# 03__EFR32_Signal_Assignments.net
KiCad netlist of a schematic drawn in Altium Designer
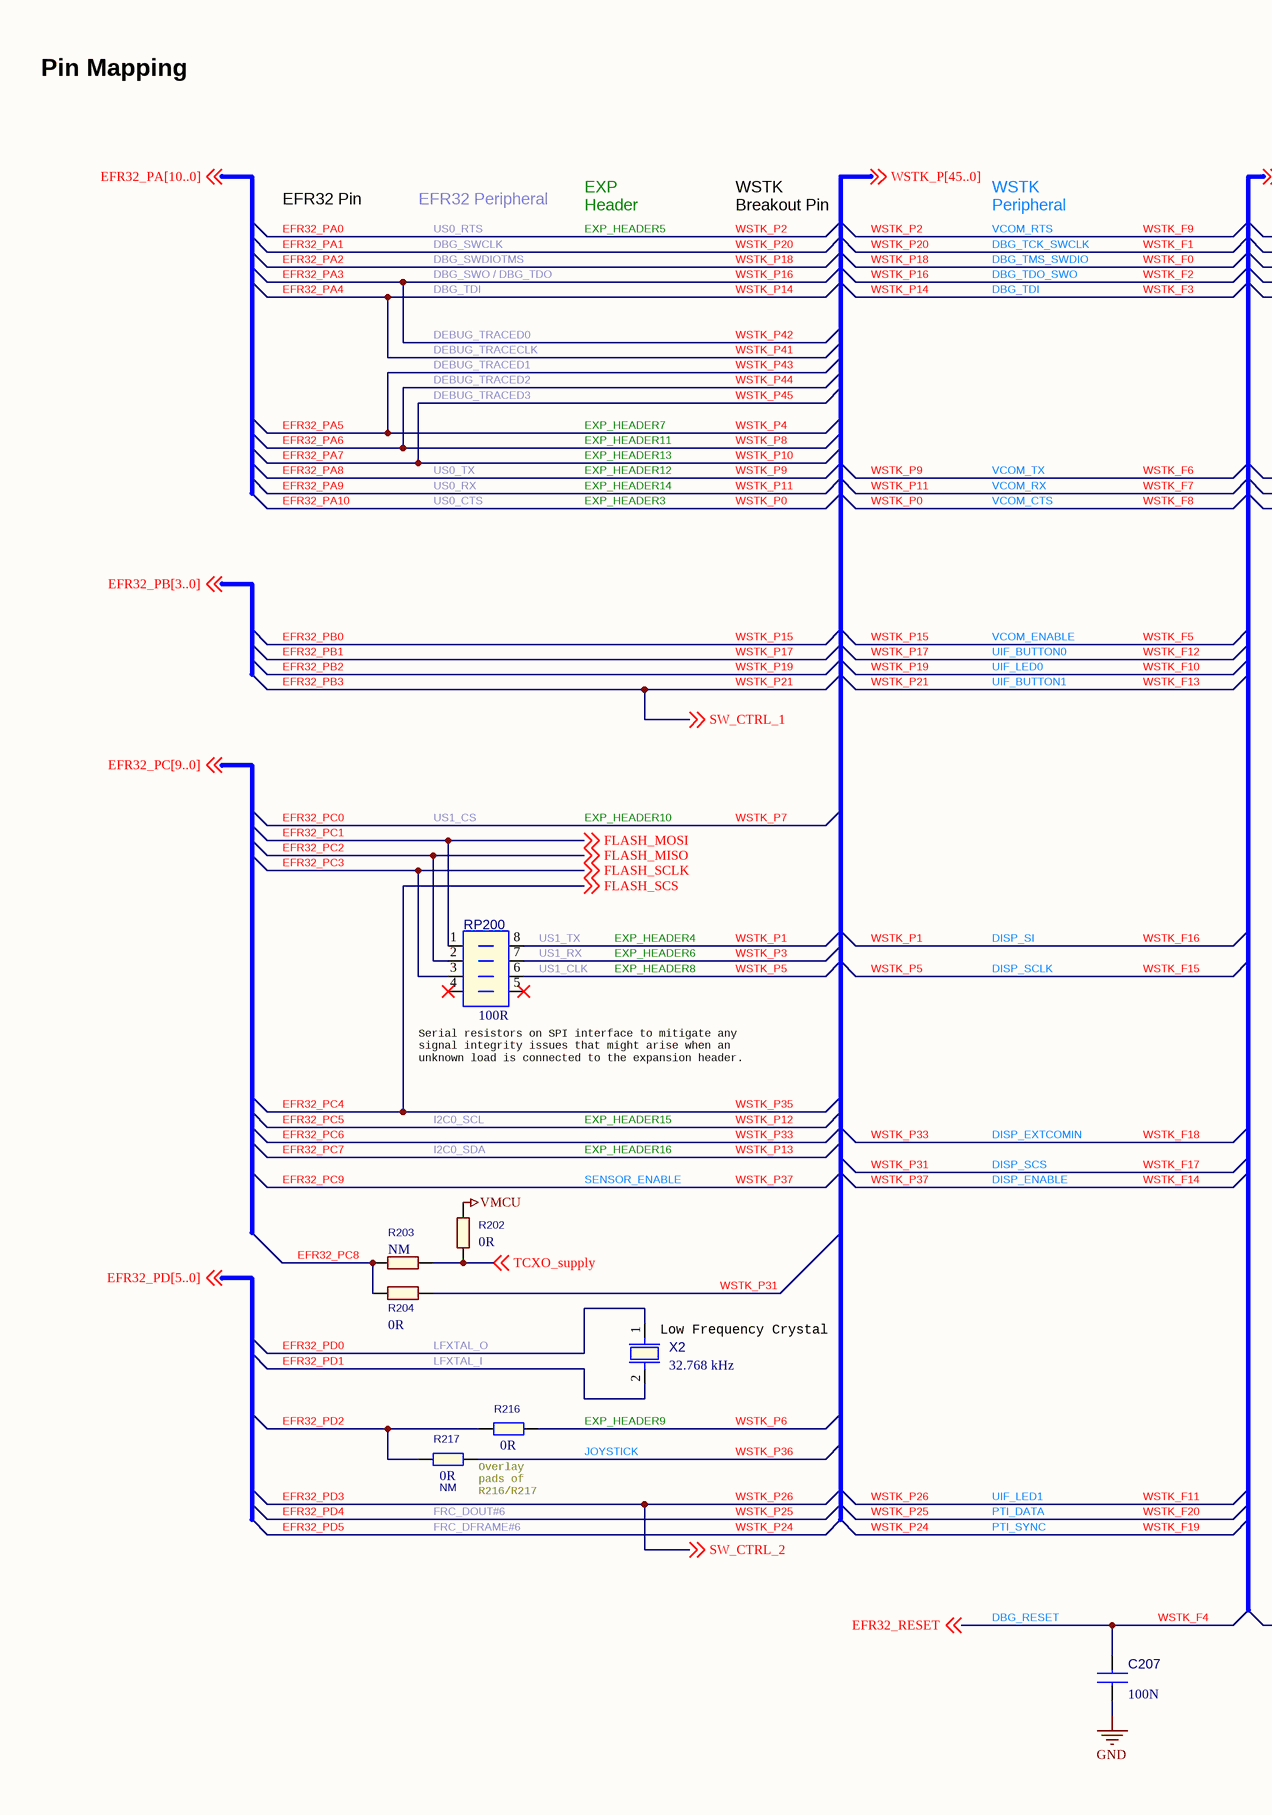
[diagram p0: 03_ EFR32 Signal Assignments.SchDoc, left]
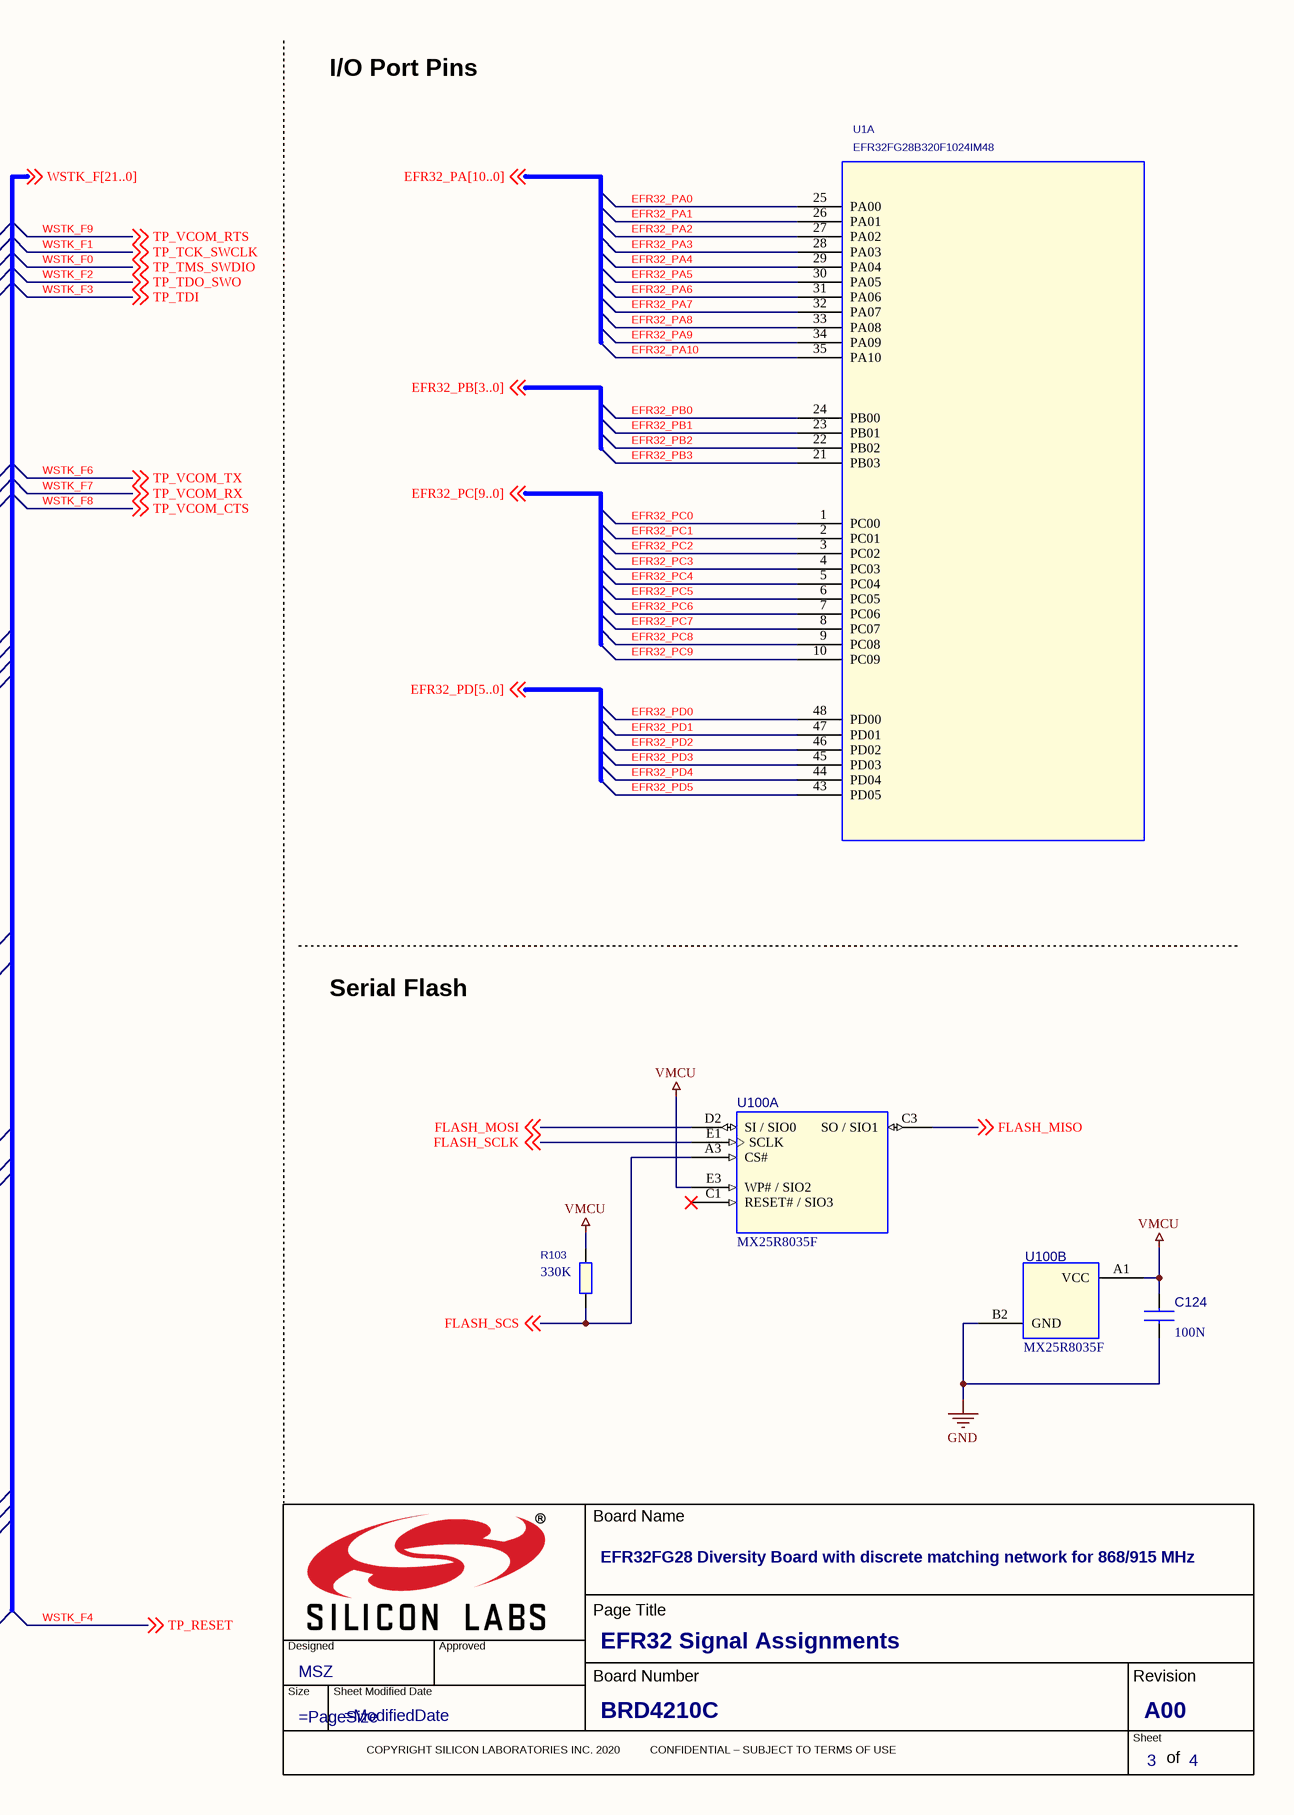
[diagram p1: 03_ EFR32 Signal Assignments.SchDoc, right]

(export (version "E")
  (design (tool "Eeschema 10.0.6"))
  (components
    (comp (ref "C124")
      (value "100N")
      (footprint "C0201_L")
      (fields (field (name "TOLERANCE") "20%"))
      (libsource (lib "*") (part "C0201"))
    )
    (comp (ref "C207")
      (value "100N")
      (footprint "C0201_L")
      (fields (field (name "TOLERANCE") "20%"))
      (libsource (lib "*") (part "C0201"))
    )
    (comp (ref "R103") (value "330K") (footprint "R0201_L") (libsource (lib "*") (part "R0201")))
    (comp (ref "R202") (value "0R") (footprint "R0201_L") (libsource (lib "") (part "R0201_1")))
    (comp (ref "R203") (value "NM") (footprint "R0201_L") (libsource (lib "BRD4210A_Library") (part "R0201")))
    (comp (ref "R204") (value "0R") (footprint "R0201_L") (libsource (lib "BRD4210A_Library") (part "R0201")))
    (comp (ref "R216") (value "0R") (footprint "R0402_L") (libsource (lib "*") (part "R0402")))
    (comp (ref "R217")
      (value "0R")
      (footprint "R0402_L")
      (fields (field (name "NOT MOUNTED") "NM"))
      (libsource (lib "*") (part "R0402"))
    )
    (comp (ref "RP200")
      (value "100R")
      (footprint "RES_MNR04-8")
      (fields (field (name "MFG") "ROHM"))
      (libsource (lib "*") (part "MNR04M0APJ101"))
    )
    (comp (ref "U1")
      (value "EFR32FG28B320F1024IM48")
      (footprint "QFN48_M040_6.0X6.0_EP_SL")
      (fields (field (name "MFG") "Silicon Labs"))
      (libsource (lib "*") (part "EFR32xG23_QFN48"))
    )
    (comp (ref "U100")
      (value "MX25R8035F")
      (footprint "BGA8_M040_1.24x1.75_WLCSP")
      (fields (field (name "MFG") "Macronix"))
      (libsource (lib "*") (part "MX25R8035"))
    )
    (comp (ref "X2")
      (value "32.768 kHz")
      (footprint "X_MCS_CM8V-T1A")
      (fields (field (name "MFG") "Micro Crystal AG"))
      (libsource (lib "*") (part "CM8V-T1A"))
    )
  )
  (nets
    (net (code "3") (name "EFR32_PC8") (class "Default")
      (node (ref "R203") (pin "2") (pinfunction "2_2") (pintype "passive"))
      (node (ref "R204") (pin "2") (pinfunction "2_2") (pintype "passive"))
      (node (ref "U1") (pin "9") (pinfunction "PC08_9") (pintype "passive"))
    )
    (net (code "5") (name "EFR32_PD0") (class "Default")
      (node (ref "U1") (pin "48") (pinfunction "PD00_48") (pintype "passive"))
      (node (ref "X2") (pin "1") (pinfunction "1_1") (pintype "passive"))
    )
    (net (code "6") (name "EFR32_PD1") (class "Default")
      (node (ref "U1") (pin "47") (pinfunction "PD01_47") (pintype "passive"))
      (node (ref "X2") (pin "2") (pinfunction "2_2") (pintype "passive"))
    )
    (net (code "7") (name "EFR32_PD2") (class "Default")
      (node (ref "R216") (pin "1") (pinfunction "1_1") (pintype "passive"))
      (node (ref "R217") (pin "1") (pinfunction "1_1") (pintype "passive"))
      (node (ref "U1") (pin "46") (pinfunction "PD02_46") (pintype "passive"))
    )
    (net (code "9") (name "EFR32_RESET") (class "Default")
      (node (ref "C207") (pin "1") (pinfunction "1_1") (pintype "passive"))
    )
    (net (code "10") (name "FLASH_MISO") (class "Default")
      (node (ref "RP200") (pin "2") (pinfunction "R12_2") (pintype "passive"))
      (node (ref "U1") (pin "3") (pinfunction "PC02_3") (pintype "passive"))
      (node (ref "U100") (pin "C3") (pinfunction "SO_/_SIO1_C3") (pintype "bidirectional"))
    )
    (net (code "11") (name "FLASH_MOSI") (class "Default")
      (node (ref "RP200") (pin "1") (pinfunction "R11_1") (pintype "passive"))
      (node (ref "U1") (pin "2") (pinfunction "PC01_2") (pintype "passive"))
      (node (ref "U100") (pin "D2") (pinfunction "SI_/_SIO0_D2") (pintype "bidirectional"))
    )
    (net (code "12") (name "FLASH_SCLK") (class "Default")
      (node (ref "RP200") (pin "3") (pinfunction "R13_3") (pintype "passive"))
      (node (ref "U1") (pin "4") (pinfunction "PC03_4") (pintype "passive"))
      (node (ref "U100") (pin "E1") (pinfunction "SCLK_E1") (pintype "input"))
    )
    (net (code "13") (name "FLASH_SCS") (class "Default")
      (node (ref "R103") (pin "1") (pinfunction "1_1") (pintype "passive"))
      (node (ref "U1") (pin "5") (pinfunction "PC04_5") (pintype "passive"))
      (node (ref "U100") (pin "A3") (pinfunction "CS#_A3") (pintype "input"))
    )
    (net (code "14") (name "GND") (class "Default")
      (node (ref "C124") (pin "2") (pinfunction "2_2") (pintype "passive"))
      (node (ref "C207") (pin "2") (pinfunction "2_2") (pintype "passive"))
      (node (ref "U100") (pin "B2") (pinfunction "GND_B2") (pintype "power_in"))
    )
    (net (code "15") (name "SW_CTRL_1") (class "Default")
      (node (ref "U1") (pin "21") (pinfunction "PB03_21") (pintype "passive"))
    )
    (net (code "16") (name "SW_CTRL_2") (class "Default")
      (node (ref "U1") (pin "45") (pinfunction "PD03_45") (pintype "passive"))
    )
    (net (code "17") (name "TCXO_supply") (class "Default")
      (node (ref "R202") (pin "1") (pinfunction "1_1") (pintype "passive"))
      (node (ref "R203") (pin "1") (pinfunction "1_1") (pintype "passive"))
    )
    (net (code "18") (name "TP_TCK_SWCLK") (class "Default")
      (node (ref "U1") (pin "26") (pinfunction "PA01_26") (pintype "passive"))
    )
    (net (code "19") (name "TP_TDI") (class "Default")
      (node (ref "U1") (pin "29") (pinfunction "PA04_29") (pintype "passive"))
    )
    (net (code "20") (name "TP_TDO_SWO") (class "Default")
      (node (ref "U1") (pin "28") (pinfunction "PA03_28") (pintype "passive"))
    )
    (net (code "21") (name "TP_TMS_SWDIO") (class "Default")
      (node (ref "U1") (pin "27") (pinfunction "PA02_27") (pintype "passive"))
    )
    (net (code "22") (name "TP_VCOM_CTS") (class "Default")
      (node (ref "U1") (pin "35") (pinfunction "PA10_35") (pintype "passive"))
    )
    (net (code "23") (name "TP_VCOM_RTS") (class "Default")
      (node (ref "U1") (pin "25") (pinfunction "PA00_25") (pintype "passive"))
    )
    (net (code "24") (name "TP_VCOM_RX") (class "Default")
      (node (ref "U1") (pin "34") (pinfunction "PA09_34") (pintype "passive"))
    )
    (net (code "25") (name "TP_VCOM_TX") (class "Default")
      (node (ref "U1") (pin "33") (pinfunction "PA08_33") (pintype "passive"))
    )
    (net (code "26") (name "VMCU") (class "Default")
      (node (ref "C124") (pin "1") (pinfunction "1_1") (pintype "passive"))
      (node (ref "R103") (pin "2") (pinfunction "2_2") (pintype "passive"))
      (node (ref "R202") (pin "2") (pinfunction "2_2") (pintype "passive"))
      (node (ref "U100") (pin "A1") (pinfunction "VCC_A1") (pintype "power_in"))
      (node (ref "U100") (pin "E3") (pinfunction "WP#_/_SIO2_E3") (pintype "input"))
    )
    (net (code "27") (name "WSTK_F5") (class "Default")
      (node (ref "U1") (pin "24") (pinfunction "PB00_24") (pintype "passive"))
    )
    (net (code "28") (name "WSTK_F10") (class "Default")
      (node (ref "U1") (pin "22") (pinfunction "PB02_22") (pintype "passive"))
    )
    (net (code "29") (name "WSTK_F12") (class "Default")
      (node (ref "U1") (pin "23") (pinfunction "PB01_23") (pintype "passive"))
    )
    (net (code "30") (name "WSTK_F14") (class "Default")
      (node (ref "U1") (pin "10") (pinfunction "PC09_10") (pintype "passive"))
    )
    (net (code "31") (name "WSTK_F15") (class "Default")
      (node (ref "RP200") (pin "6") (pinfunction "R16_6") (pintype "passive"))
    )
    (net (code "32") (name "WSTK_F16") (class "Default")
      (node (ref "RP200") (pin "8") (pinfunction "R18_8") (pintype "passive"))
    )
    (net (code "33") (name "WSTK_F17") (class "Default")
      (node (ref "R204") (pin "1") (pinfunction "1_1") (pintype "passive"))
    )
    (net (code "34") (name "WSTK_F18") (class "Default")
      (node (ref "U1") (pin "7") (pinfunction "PC06_7") (pintype "passive"))
    )
    (net (code "35") (name "WSTK_F19") (class "Default")
      (node (ref "U1") (pin "43") (pinfunction "PD05_43") (pintype "passive"))
    )
    (net (code "36") (name "WSTK_F20") (class "Default")
      (node (ref "U1") (pin "44") (pinfunction "PD04_44") (pintype "passive"))
    )
    (net (code "38") (name "WSTK_P3") (class "Default")
      (node (ref "RP200") (pin "7") (pinfunction "R17_7") (pintype "passive"))
    )
    (net (code "39") (name "WSTK_P6") (class "Default")
      (node (ref "R216") (pin "2") (pinfunction "2_2") (pintype "passive"))
    )
    (net (code "40") (name "WSTK_P7") (class "Default")
      (node (ref "U1") (pin "1") (pinfunction "PC00_1") (pintype "passive"))
    )
    (net (code "41") (name "WSTK_P8") (class "Default")
      (node (ref "U1") (pin "31") (pinfunction "PA06_31") (pintype "passive"))
    )
    (net (code "42") (name "WSTK_P12") (class "Default")
      (node (ref "U1") (pin "6") (pinfunction "PC05_6") (pintype "passive"))
    )
    (net (code "43") (name "WSTK_P13") (class "Default")
      (node (ref "U1") (pin "8") (pinfunction "PC07_8") (pintype "passive"))
    )
    (net (code "44") (name "WSTK_P36") (class "Default")
      (node (ref "R217") (pin "2") (pinfunction "2_2") (pintype "passive"))
    )
    (net (code "45") (name "WSTK_P43") (class "Default")
      (node (ref "U1") (pin "30") (pinfunction "PA05_30") (pintype "passive"))
    )
    (net (code "46") (name "WSTK_P45") (class "Default")
      (node (ref "U1") (pin "32") (pinfunction "PA07_32") (pintype "passive"))
    )
    (net (code "48") (name "unconnected-(RP200-R14-Pad4)") (class "Default")
      (node (ref "RP200") (pin "4") (pinfunction "R14_4") (pintype "passive+no_connect"))
    )
    (net (code "49") (name "unconnected-(RP200-R15-Pad5)") (class "Default")
      (node (ref "RP200") (pin "5") (pinfunction "R15_5") (pintype "passive+no_connect"))
    )
    (net (code "50") (name "unconnected-(U100A-RESET#_{slash}_SIO3-PadC1)") (class "Default")
      (node (ref "U100") (pin "C1") (pinfunction "RESET#_/_SIO3_C1") (pintype "input+no_connect"))
    )
  )
)
